# octanis_eps_revised.net
KiCad netlist of a schematic drawn in EAGLE
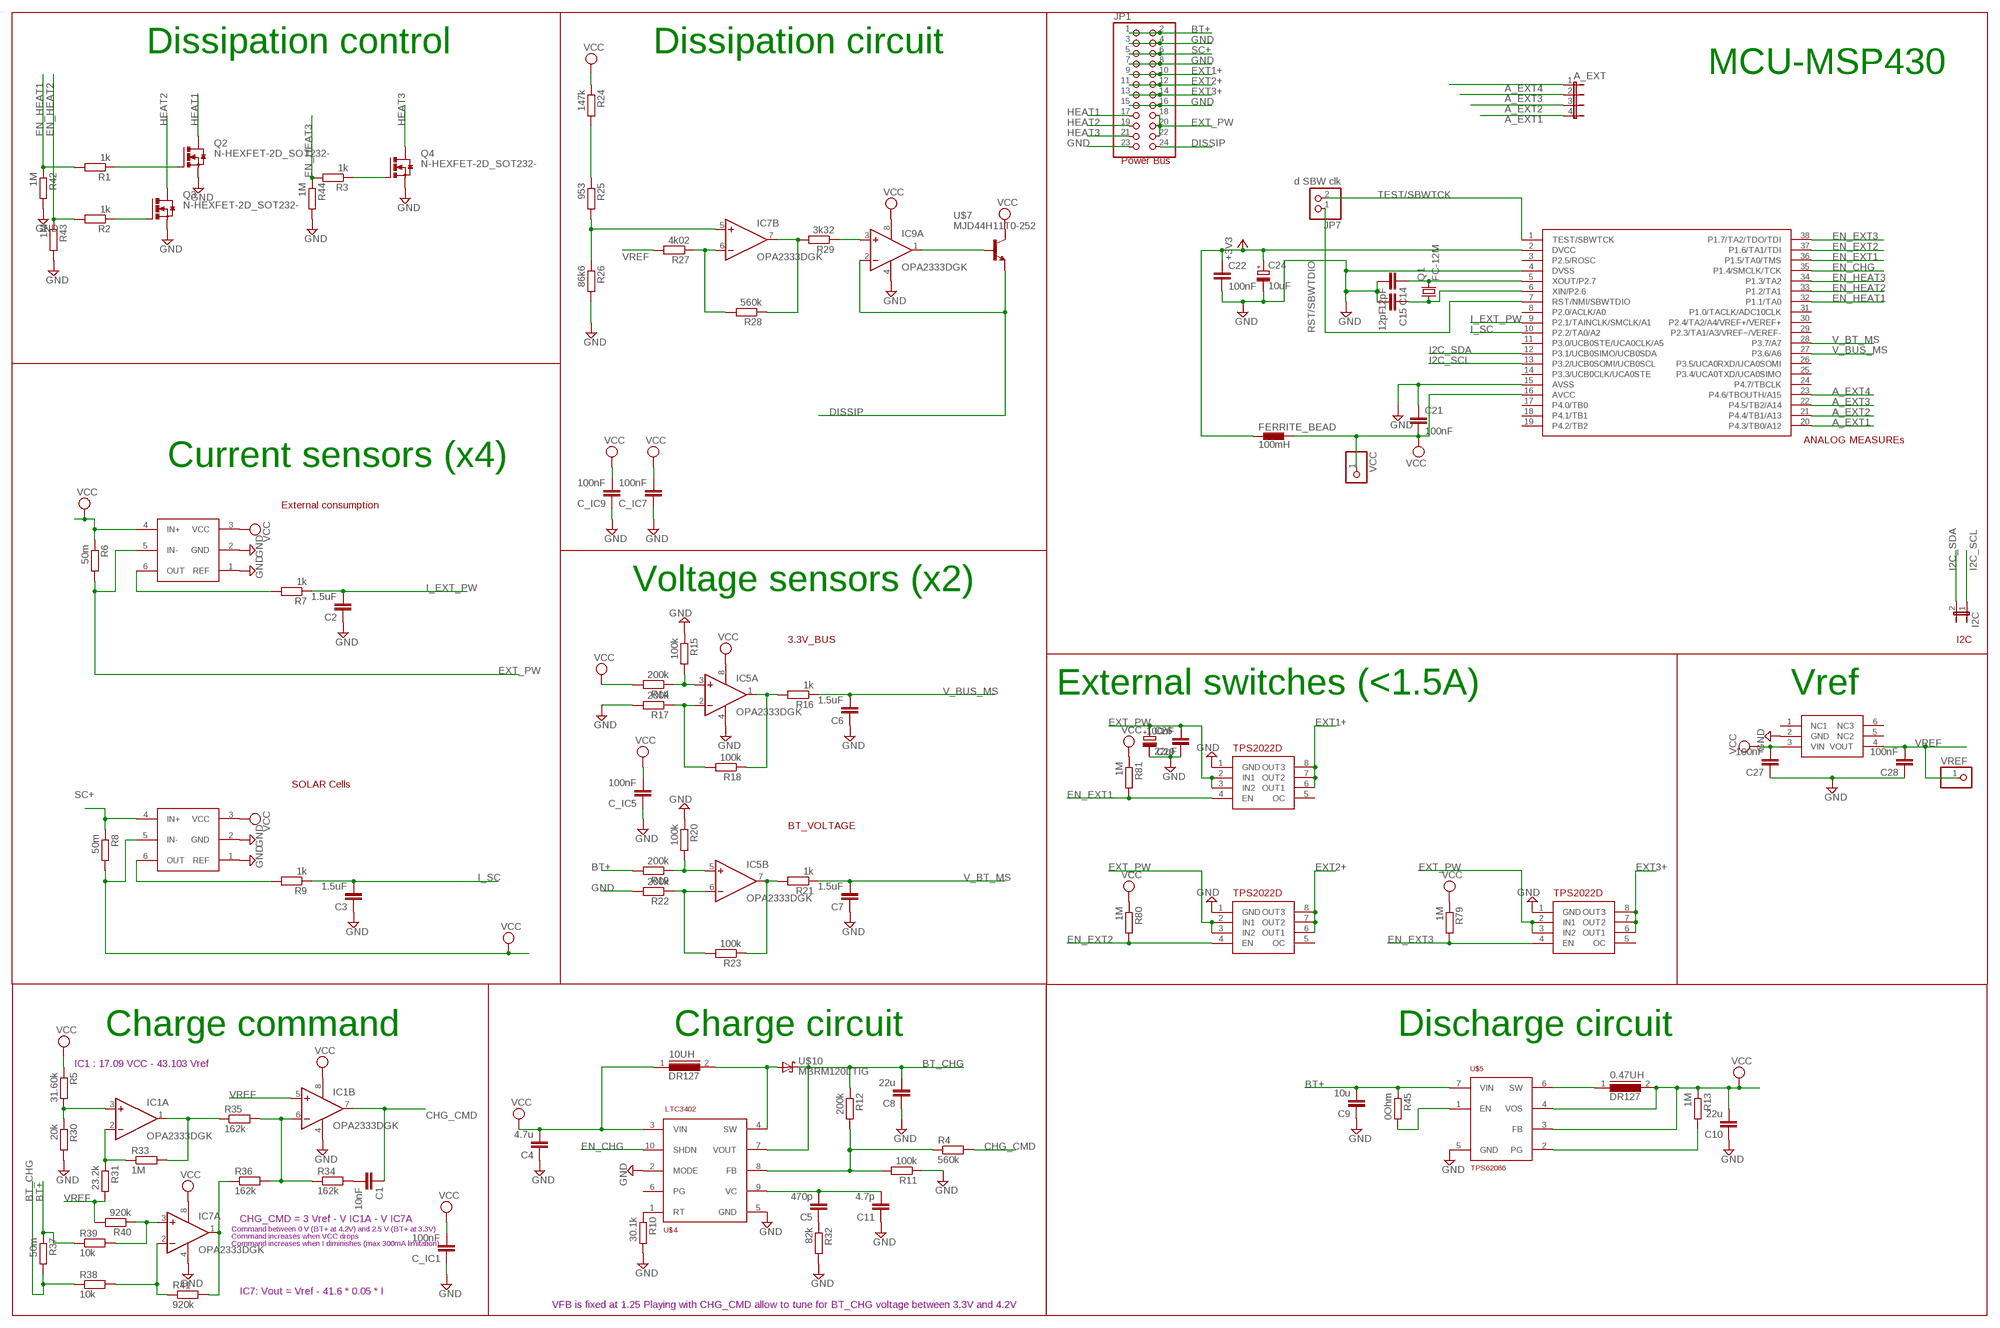
[diagram p0: schematic, sheet 1]

(export (version "E")
  (design (tool "Eeschema 10.0.6"))
  (components
    (comp (ref "0.47UH")
      (value "DR127")
      (footprint "eagle-import:DR127")
      (libsource (lib "eagle-import") (part "DR127"))
    )
    (comp (ref "10UH")
      (value "DR127")
      (footprint "eagle-import:DR127")
      (libsource (lib "eagle-import") (part "DR127"))
    )
    (comp (ref "A_EXT")
      (value "JP4E")
      (footprint "eagle-import:JP4")
      (libsource (lib "eagle-import") (part "JP4E"))
    )
    (comp (ref "C1")
      (value "10nF")
      (footprint "eagle-import:C0603")
      (libsource (lib "eagle-import") (part "C-EUC0603"))
    )
    (comp (ref "C2")
      (value "1.5uF")
      (footprint "eagle-import:C0603")
      (libsource (lib "eagle-import") (part "C-EUC0603"))
    )
    (comp (ref "C3")
      (value "1.5uF")
      (footprint "eagle-import:C0603")
      (libsource (lib "eagle-import") (part "C-EUC0603"))
    )
    (comp (ref "C4")
      (value "4.7u")
      (footprint "eagle-import:C1206")
      (libsource (lib "eagle-import") (part "C-EUC1206"))
    )
    (comp (ref "C5")
      (value "470p")
      (footprint "eagle-import:C0603")
      (libsource (lib "eagle-import") (part "C-EUC0603"))
    )
    (comp (ref "C6")
      (value "1.5uF")
      (footprint "eagle-import:C0603")
      (libsource (lib "eagle-import") (part "C-EUC0603"))
    )
    (comp (ref "C7")
      (value "1.5uF")
      (footprint "eagle-import:C0603")
      (libsource (lib "eagle-import") (part "C-EUC0603"))
    )
    (comp (ref "C8")
      (value "22u")
      (footprint "eagle-import:C0603")
      (libsource (lib "eagle-import") (part "C-EUC0603"))
    )
    (comp (ref "C9")
      (value "10u")
      (footprint "eagle-import:C1206")
      (libsource (lib "eagle-import") (part "C-EUC1206"))
    )
    (comp (ref "C10")
      (value "22u")
      (footprint "eagle-import:C1206")
      (libsource (lib "eagle-import") (part "C-EUC1206"))
    )
    (comp (ref "C11")
      (value "4.7p")
      (footprint "eagle-import:C0603")
      (libsource (lib "eagle-import") (part "C-EUC0603"))
    )
    (comp (ref "C14")
      (value "12pF")
      (footprint "eagle-import:C0603")
      (libsource (lib "eagle-import") (part "C-EUC0603"))
    )
    (comp (ref "C15")
      (value "12pF")
      (footprint "eagle-import:C0603")
      (libsource (lib "eagle-import") (part "C-EUC0603"))
    )
    (comp (ref "C21")
      (value "100nF")
      (footprint "eagle-import:C0603")
      (libsource (lib "eagle-import") (part "C-EUC0603"))
    )
    (comp (ref "C22")
      (value "100nF")
      (footprint "eagle-import:C0603")
      (libsource (lib "eagle-import") (part "C-EUC0603"))
    )
    (comp (ref "C24")
      (value "10uF")
      (footprint "eagle-import:A_3216-18R")
      (libsource (lib "eagle-import") (part "CPOL-EUA/3216-18R"))
    )
    (comp (ref "C26")
      (value "22uF")
      (footprint "eagle-import:A_3216-18R")
      (libsource (lib "eagle-import") (part "CPOL-EUA/3216-18R"))
    )
    (comp (ref "C27")
      (value "100nF")
      (footprint "eagle-import:C0603")
      (libsource (lib "eagle-import") (part "C-EUC0603"))
    )
    (comp (ref "C28")
      (value "100nF")
      (footprint "eagle-import:C0603")
      (libsource (lib "eagle-import") (part "C-EUC0603"))
    )
    (comp (ref "C29")
      (value "100nF")
      (footprint "eagle-import:C0603")
      (libsource (lib "eagle-import") (part "C-EUC0603"))
    )
    (comp (ref "C_IC1")
      (value "100nF")
      (footprint "eagle-import:C0603")
      (libsource (lib "eagle-import") (part "C-EUC0603"))
    )
    (comp (ref "C_IC5")
      (value "100nF")
      (footprint "eagle-import:C0603")
      (libsource (lib "eagle-import") (part "C-EUC0603"))
    )
    (comp (ref "C_IC7")
      (value "100nF")
      (footprint "eagle-import:C0603")
      (libsource (lib "eagle-import") (part "C-EUC0603"))
    )
    (comp (ref "C_IC9")
      (value "100nF")
      (footprint "eagle-import:C0603")
      (libsource (lib "eagle-import") (part "C-EUC0603"))
    )
    (comp (ref "FERRITE_BEAD")
      (value "100mH")
      (footprint "eagle-import:0402")
      (libsource (lib "eagle-import") (part "BLM15HD601SN1"))
    )
    (comp (ref "I2C")
      (value "JP1E")
      (footprint "eagle-import:JP1")
      (libsource (lib "eagle-import") (part "JP1E"))
    )
    (comp (ref "IC1")
      (value "OPA2333DGK")
      (footprint "eagle-import:MSOP08")
      (libsource (lib "eagle-import") (part "OPA2333DGK"))
    )
    (comp (ref "IC5")
      (value "OPA2333DGK")
      (footprint "eagle-import:MSOP08")
      (libsource (lib "eagle-import") (part "OPA2333DGK"))
    )
    (comp (ref "IC7")
      (value "OPA2333DGK")
      (footprint "eagle-import:MSOP08")
      (libsource (lib "eagle-import") (part "OPA2333DGK"))
    )
    (comp (ref "IC9")
      (value "OPA2333DGK")
      (footprint "eagle-import:MSOP08")
      (libsource (lib "eagle-import") (part "OPA2333DGK"))
    )
    (comp (ref "JP1")
      (value "PINHD-2X12")
      (footprint "eagle-import:2X12")
      (libsource (lib "eagle-import") (part "PINHD-2X12"))
    )
    (comp (ref "JP7")
      (value "d SBW clk")
      (footprint "eagle-import:1X02")
      (libsource (lib "eagle-import") (part "PINHD-1X2"))
    )
    (comp (ref "Q1")
      (value "FC-12M")
      (footprint "eagle-import:FC-12M")
      (libsource (lib "eagle-import") (part "FC-12M"))
    )
    (comp (ref "Q2")
      (value "N-HEXFET-2D_SOT232-")
      (footprint "eagle-import:SOT223")
      (libsource (lib "eagle-import") (part "N-HEXFET-2D_?-SOT232"))
    )
    (comp (ref "Q3")
      (value "N-HEXFET-2D_SOT232-")
      (footprint "eagle-import:SOT223")
      (libsource (lib "eagle-import") (part "N-HEXFET-2D_?-SOT232"))
    )
    (comp (ref "Q4")
      (value "N-HEXFET-2D_SOT232-")
      (footprint "eagle-import:SOT223")
      (libsource (lib "eagle-import") (part "N-HEXFET-2D_?-SOT232"))
    )
    (comp (ref "R1")
      (value "1k")
      (footprint "eagle-import:R0603")
      (libsource (lib "eagle-import") (part "R-EU_R0603"))
    )
    (comp (ref "R2")
      (value "1k")
      (footprint "eagle-import:R0603")
      (libsource (lib "eagle-import") (part "R-EU_R0603"))
    )
    (comp (ref "R3")
      (value "1k")
      (footprint "eagle-import:R0603")
      (libsource (lib "eagle-import") (part "R-EU_R0603"))
    )
    (comp (ref "R4")
      (value "560k")
      (footprint "eagle-import:R0603")
      (libsource (lib "eagle-import") (part "R-EU_R0603"))
    )
    (comp (ref "R5")
      (value "31.60k")
      (footprint "eagle-import:R0603")
      (libsource (lib "eagle-import") (part "R-EU_R0603"))
    )
    (comp (ref "R6")
      (value "50m")
      (footprint "eagle-import:R1206")
      (libsource (lib "eagle-import") (part "R-EU_R1206"))
    )
    (comp (ref "R7")
      (value "1k")
      (footprint "eagle-import:R0603")
      (libsource (lib "eagle-import") (part "R-EU_R0603"))
    )
    (comp (ref "R8")
      (value "50m")
      (footprint "eagle-import:R1206")
      (libsource (lib "eagle-import") (part "R-EU_R1206"))
    )
    (comp (ref "R9")
      (value "1k")
      (footprint "eagle-import:R0603")
      (libsource (lib "eagle-import") (part "R-EU_R0603"))
    )
    (comp (ref "R10")
      (value "30.1k")
      (footprint "eagle-import:R0603")
      (libsource (lib "eagle-import") (part "R-EU_R0603"))
    )
    (comp (ref "R11")
      (value "100k")
      (footprint "eagle-import:R0603")
      (libsource (lib "eagle-import") (part "R-EU_R0603"))
    )
    (comp (ref "R12")
      (value "200k")
      (footprint "eagle-import:R0603")
      (libsource (lib "eagle-import") (part "R-EU_R0603"))
    )
    (comp (ref "R13")
      (value "1M")
      (footprint "eagle-import:R0603")
      (libsource (lib "eagle-import") (part "R-EU_R0603"))
    )
    (comp (ref "R14")
      (value "200k")
      (footprint "eagle-import:R0603")
      (libsource (lib "eagle-import") (part "R-EU_R0603"))
    )
    (comp (ref "R15")
      (value "100k")
      (footprint "eagle-import:R0603")
      (libsource (lib "eagle-import") (part "R-EU_R0603"))
    )
    (comp (ref "R16")
      (value "1k")
      (footprint "eagle-import:R0603")
      (libsource (lib "eagle-import") (part "R-EU_R0603"))
    )
    (comp (ref "R17")
      (value "200k")
      (footprint "eagle-import:R0603")
      (libsource (lib "eagle-import") (part "R-EU_R0603"))
    )
    (comp (ref "R18")
      (value "100k")
      (footprint "eagle-import:R0603")
      (libsource (lib "eagle-import") (part "R-EU_R0603"))
    )
    (comp (ref "R19")
      (value "200k")
      (footprint "eagle-import:R0603")
      (libsource (lib "eagle-import") (part "R-EU_R0603"))
    )
    (comp (ref "R20")
      (value "100k")
      (footprint "eagle-import:R0603")
      (libsource (lib "eagle-import") (part "R-EU_R0603"))
    )
    (comp (ref "R21")
      (value "1k")
      (footprint "eagle-import:R0603")
      (libsource (lib "eagle-import") (part "R-EU_R0603"))
    )
    (comp (ref "R22")
      (value "200k")
      (footprint "eagle-import:R0603")
      (libsource (lib "eagle-import") (part "R-EU_R0603"))
    )
    (comp (ref "R23")
      (value "100k")
      (footprint "eagle-import:R0603")
      (libsource (lib "eagle-import") (part "R-EU_R0603"))
    )
    (comp (ref "R24")
      (value "147k")
      (footprint "eagle-import:R0603")
      (libsource (lib "eagle-import") (part "R-EU_R0603"))
    )
    (comp (ref "R25")
      (value "953")
      (footprint "eagle-import:R0603")
      (libsource (lib "eagle-import") (part "R-EU_R0603"))
    )
    (comp (ref "R26")
      (value "86k6")
      (footprint "eagle-import:R0603")
      (libsource (lib "eagle-import") (part "R-EU_R0603"))
    )
    (comp (ref "R27")
      (value "4k02")
      (footprint "eagle-import:R0603")
      (libsource (lib "eagle-import") (part "R-EU_R0603"))
    )
    (comp (ref "R28")
      (value "560k")
      (footprint "eagle-import:R0603")
      (libsource (lib "eagle-import") (part "R-EU_R0603"))
    )
    (comp (ref "R29")
      (value "3k32")
      (footprint "eagle-import:R0603")
      (libsource (lib "eagle-import") (part "R-EU_R0603"))
    )
    (comp (ref "R30")
      (value "20k")
      (footprint "eagle-import:R0603")
      (libsource (lib "eagle-import") (part "R-EU_R0603"))
    )
    (comp (ref "R31")
      (value "23.2k")
      (footprint "eagle-import:R0603")
      (libsource (lib "eagle-import") (part "R-EU_R0603"))
    )
    (comp (ref "R32")
      (value "82k")
      (footprint "eagle-import:R0603")
      (libsource (lib "eagle-import") (part "R-EU_R0603"))
    )
    (comp (ref "R33")
      (value "1M")
      (footprint "eagle-import:R0603")
      (libsource (lib "eagle-import") (part "R-EU_R0603"))
    )
    (comp (ref "R34")
      (value "162k")
      (footprint "eagle-import:R0603")
      (libsource (lib "eagle-import") (part "R-EU_R0603"))
    )
    (comp (ref "R35")
      (value "162k")
      (footprint "eagle-import:R0603")
      (libsource (lib "eagle-import") (part "R-EU_R0603"))
    )
    (comp (ref "R36")
      (value "162k")
      (footprint "eagle-import:R0603")
      (libsource (lib "eagle-import") (part "R-EU_R0603"))
    )
    (comp (ref "R37")
      (value "50m")
      (footprint "eagle-import:R1206")
      (libsource (lib "eagle-import") (part "R-EU_R1206"))
    )
    (comp (ref "R38")
      (value "10k")
      (footprint "eagle-import:R0603")
      (libsource (lib "eagle-import") (part "R-EU_R0603"))
    )
    (comp (ref "R39")
      (value "10k")
      (footprint "eagle-import:R0603")
      (libsource (lib "eagle-import") (part "R-EU_R0603"))
    )
    (comp (ref "R40")
      (value "920k")
      (footprint "eagle-import:R0603")
      (libsource (lib "eagle-import") (part "R-EU_R0603"))
    )
    (comp (ref "R41")
      (value "920k")
      (footprint "eagle-import:R0603")
      (libsource (lib "eagle-import") (part "R-EU_R0603"))
    )
    (comp (ref "R42")
      (value "1M")
      (footprint "eagle-import:R0603")
      (libsource (lib "eagle-import") (part "R-EU_R0603"))
    )
    (comp (ref "R43")
      (value "1M")
      (footprint "eagle-import:R0603")
      (libsource (lib "eagle-import") (part "R-EU_R0603"))
    )
    (comp (ref "R44")
      (value "1M")
      (footprint "eagle-import:R0603")
      (libsource (lib "eagle-import") (part "R-EU_R0603"))
    )
    (comp (ref "R45")
      (value "0Ohm")
      (footprint "eagle-import:R0603")
      (libsource (lib "eagle-import") (part "R-EU_R0603"))
    )
    (comp (ref "R79")
      (value "1M")
      (footprint "eagle-import:R0603")
      (libsource (lib "eagle-import") (part "R-EU_R0603"))
    )
    (comp (ref "R80")
      (value "1M")
      (footprint "eagle-import:R0603")
      (libsource (lib "eagle-import") (part "R-EU_R0603"))
    )
    (comp (ref "R81")
      (value "1M")
      (footprint "eagle-import:R0603")
      (libsource (lib "eagle-import") (part "R-EU_R0603"))
    )
    (comp (ref "U$2")
      (value "INA213")
      (footprint "eagle-import:SC70-6")
      (libsource (lib "eagle-import") (part "INA213"))
    )
    (comp (ref "U$3")
      (value "INA213")
      (footprint "eagle-import:SC70-6")
      (libsource (lib "eagle-import") (part "INA213"))
    )
    (comp (ref "U$4")
      (value "LTC3402")
      (footprint "eagle-import:MSOP10")
      (libsource (lib "eagle-import") (part "LTC3402"))
    )
    (comp (ref "U$5")
      (value "TPS62086")
      (footprint "eagle-import:QFN-7")
      (libsource (lib "eagle-import") (part "TPS62086"))
    )
    (comp (ref "U$6")
      (value "MSP430G2544")
      (footprint "eagle-import:TSSOP38")
      (libsource (lib "eagle-import") (part "MSP430G2544"))
    )
    (comp (ref "U$7")
      (value "MJD44H11T0-252")
      (footprint "eagle-import:TO252")
      (libsource (lib "eagle-import") (part "MJD44H11T0-252"))
    )
    (comp (ref "U$10")
      (value "MBRM120LTIG")
      (footprint "eagle-import:DO216AA")
      (libsource (lib "eagle-import") (part "MBRM120LTIG"))
    )
    (comp (ref "U$16")
      (value "TPS2022D")
      (footprint "eagle-import:SO8")
      (libsource (lib "eagle-import") (part "TPS2022D"))
    )
    (comp (ref "U$17")
      (value "TPS2022D")
      (footprint "eagle-import:SO8")
      (libsource (lib "eagle-import") (part "TPS2022D"))
    )
    (comp (ref "U$18")
      (value "TPS2022D")
      (footprint "eagle-import:SO8")
      (libsource (lib "eagle-import") (part "TPS2022D"))
    )
    (comp (ref "U$19")
      (value "ADR127B")
      (footprint "eagle-import:TSOT23-6")
      (libsource (lib "eagle-import") (part "ADR127B"))
    )
    (comp (ref "VCC")
      (value "PINHD-1X1")
      (footprint "eagle-import:1X01")
      (libsource (lib "eagle-import") (part "PINHD-1X1"))
    )
    (comp (ref "VREF")
      (value "PINHD-1X1")
      (footprint "eagle-import:1X01")
      (libsource (lib "eagle-import") (part "PINHD-1X1"))
    )
  )
  (nets
    (net (code "1") (name "+3V3") (class "Default")
      (node (ref "C22") (pin "1") (pinfunction "1_1") (pintype "passive"))
      (node (ref "C24") (pin "+") (pinfunction "+_+") (pintype "passive"))
      (node (ref "FERRITE_BEAD") (pin "1") (pinfunction "1_1") (pintype "passive"))
      (node (ref "U$6") (pin "2") (pinfunction "DVCC_2") (pintype "bidirectional"))
    )
    (net (code "2") (name "/A_EXT1") (class "Default")
      (node (ref "A_EXT") (pin "4") (pinfunction "4_4") (pintype "passive"))
      (node (ref "U$6") (pin "20") (pinfunction "P4.3/TB0/A12_20") (pintype "bidirectional"))
    )
    (net (code "3") (name "/A_EXT2") (class "Default")
      (node (ref "A_EXT") (pin "3") (pinfunction "3_3") (pintype "passive"))
      (node (ref "U$6") (pin "21") (pinfunction "P4.4/TB1/A13_21") (pintype "bidirectional"))
    )
    (net (code "4") (name "/A_EXT3") (class "Default")
      (node (ref "A_EXT") (pin "2") (pinfunction "2_2") (pintype "passive"))
      (node (ref "U$6") (pin "22") (pinfunction "P4.5/TB2/A14_22") (pintype "bidirectional"))
    )
    (net (code "5") (name "/A_EXT4") (class "Default")
      (node (ref "A_EXT") (pin "1") (pinfunction "1_1") (pintype "passive"))
      (node (ref "U$6") (pin "23") (pinfunction "P4.6/TBOUTH/A15_23") (pintype "bidirectional"))
    )
    (net (code "6") (name "/BT+") (class "Default")
      (node (ref "C9") (pin "2") (pinfunction "2_2") (pintype "passive"))
      (node (ref "JP1") (pin "1") (pinfunction "1_1") (pintype "passive"))
      (node (ref "JP1") (pin "2") (pinfunction "2_2") (pintype "passive"))
      (node (ref "R19") (pin "2") (pinfunction "2_2") (pintype "passive"))
      (node (ref "R37") (pin "1") (pinfunction "1_1") (pintype "passive"))
      (node (ref "R39") (pin "1") (pinfunction "1_1") (pintype "passive"))
      (node (ref "R45") (pin "1") (pinfunction "1_1") (pintype "passive"))
      (node (ref "U$5") (pin "7") (pinfunction "VIN_7") (pintype "bidirectional"))
    )
    (net (code "7") (name "/BT_CHG") (class "Default")
      (node (ref "C8") (pin "2") (pinfunction "2_2") (pintype "passive"))
      (node (ref "R12") (pin "1") (pinfunction "1_1") (pintype "passive"))
      (node (ref "R37") (pin "2") (pinfunction "2_2") (pintype "passive"))
      (node (ref "R38") (pin "1") (pinfunction "1_1") (pintype "passive"))
      (node (ref "U$10") (pin "C") (pinfunction "K_C") (pintype "passive"))
      (node (ref "U$4") (pin "7") (pinfunction "VOUT_7") (pintype "bidirectional"))
    )
    (net (code "8") (name "/CHG_CMD") (class "Default")
      (node (ref "C1") (pin "1") (pinfunction "1_1") (pintype "passive"))
      (node (ref "IC1") (pin "7") (pinfunction "OUT_7") (pintype "output"))
      (node (ref "R4") (pin "2") (pinfunction "2_2") (pintype "passive"))
    )
    (net (code "9") (name "/DISSIP") (class "Default")
      (node (ref "IC9") (pin "2") (pinfunction "-IN_2") (pintype "input"))
      (node (ref "JP1") (pin "24") (pinfunction "24_24") (pintype "passive"))
      (node (ref "U$7") (pin "3") (pinfunction "E_3") (pintype "passive"))
    )
    (net (code "10") (name "/EN_CHG") (class "Default")
      (node (ref "U$4") (pin "10") (pinfunction "SHDN_10") (pintype "bidirectional"))
      (node (ref "U$6") (pin "35") (pinfunction "P1.4/SMCLK/TCK_35") (pintype "bidirectional"))
    )
    (net (code "11") (name "/EN_EXT1") (class "Default")
      (node (ref "R81") (pin "2") (pinfunction "2_2") (pintype "passive"))
      (node (ref "U$16") (pin "4") (pinfunction "EN_4") (pintype "bidirectional"))
      (node (ref "U$6") (pin "36") (pinfunction "P1.5/TA0/TMS_36") (pintype "bidirectional"))
    )
    (net (code "12") (name "/EN_EXT2") (class "Default")
      (node (ref "R80") (pin "2") (pinfunction "2_2") (pintype "passive"))
      (node (ref "U$17") (pin "4") (pinfunction "EN_4") (pintype "bidirectional"))
      (node (ref "U$6") (pin "37") (pinfunction "P1.6/TA1/TDI_37") (pintype "bidirectional"))
    )
    (net (code "13") (name "/EN_EXT3") (class "Default")
      (node (ref "R79") (pin "2") (pinfunction "2_2") (pintype "passive"))
      (node (ref "U$18") (pin "4") (pinfunction "EN_4") (pintype "bidirectional"))
      (node (ref "U$6") (pin "38") (pinfunction "P1.7/TA2/TDO/TDI_38") (pintype "bidirectional"))
    )
    (net (code "14") (name "/EN_HEAT1") (class "Default")
      (node (ref "R1") (pin "2") (pinfunction "2_2") (pintype "passive"))
      (node (ref "R42") (pin "1") (pinfunction "1_1") (pintype "passive"))
      (node (ref "U$6") (pin "32") (pinfunction "P1.1/TA0_32") (pintype "bidirectional"))
    )
    (net (code "15") (name "/EN_HEAT2") (class "Default")
      (node (ref "R2") (pin "2") (pinfunction "2_2") (pintype "passive"))
      (node (ref "R43") (pin "1") (pinfunction "1_1") (pintype "passive"))
      (node (ref "U$6") (pin "33") (pinfunction "P1.2/TA1_33") (pintype "bidirectional"))
    )
    (net (code "16") (name "/EN_HEAT3") (class "Default")
      (node (ref "R3") (pin "2") (pinfunction "2_2") (pintype "passive"))
      (node (ref "R44") (pin "1") (pinfunction "1_1") (pintype "passive"))
      (node (ref "U$6") (pin "34") (pinfunction "P1.3/TA2_34") (pintype "bidirectional"))
    )
    (net (code "17") (name "/EXT1+") (class "Default")
      (node (ref "JP1") (pin "10") (pinfunction "10_10") (pintype "passive"))
      (node (ref "JP1") (pin "9") (pinfunction "9_9") (pintype "passive"))
      (node (ref "U$16") (pin "6") (pinfunction "OUT1_6") (pintype "bidirectional"))
      (node (ref "U$16") (pin "7") (pinfunction "OUT2_7") (pintype "bidirectional"))
      (node (ref "U$16") (pin "8") (pinfunction "OUT3_8") (pintype "bidirectional"))
    )
    (net (code "18") (name "/EXT2+") (class "Default")
      (node (ref "JP1") (pin "11") (pinfunction "11_11") (pintype "passive"))
      (node (ref "JP1") (pin "12") (pinfunction "12_12") (pintype "passive"))
      (node (ref "U$17") (pin "6") (pinfunction "OUT1_6") (pintype "bidirectional"))
      (node (ref "U$17") (pin "7") (pinfunction "OUT2_7") (pintype "bidirectional"))
      (node (ref "U$17") (pin "8") (pinfunction "OUT3_8") (pintype "bidirectional"))
    )
    (net (code "19") (name "/EXT3+") (class "Default")
      (node (ref "JP1") (pin "13") (pinfunction "13_13") (pintype "passive"))
      (node (ref "JP1") (pin "14") (pinfunction "14_14") (pintype "passive"))
      (node (ref "U$18") (pin "6") (pinfunction "OUT1_6") (pintype "bidirectional"))
      (node (ref "U$18") (pin "7") (pinfunction "OUT2_7") (pintype "bidirectional"))
      (node (ref "U$18") (pin "8") (pinfunction "OUT3_8") (pintype "bidirectional"))
    )
    (net (code "20") (name "/EXT_PW") (class "Default")
      (node (ref "C26") (pin "+") (pinfunction "+_+") (pintype "passive"))
      (node (ref "C29") (pin "2") (pinfunction "2_2") (pintype "passive"))
      (node (ref "JP1") (pin "18") (pinfunction "18_18") (pintype "passive"))
      (node (ref "JP1") (pin "20") (pinfunction "20_20") (pintype "passive"))
      (node (ref "JP1") (pin "22") (pinfunction "22_22") (pintype "passive"))
      (node (ref "R6") (pin "2") (pinfunction "2_2") (pintype "passive"))
      (node (ref "U$16") (pin "2") (pinfunction "IN1_2") (pintype "bidirectional"))
      (node (ref "U$16") (pin "3") (pinfunction "IN2_3") (pintype "bidirectional"))
      (node (ref "U$17") (pin "2") (pinfunction "IN1_2") (pintype "bidirectional"))
      (node (ref "U$17") (pin "3") (pinfunction "IN2_3") (pintype "bidirectional"))
      (node (ref "U$18") (pin "2") (pinfunction "IN1_2") (pintype "bidirectional"))
      (node (ref "U$18") (pin "3") (pinfunction "IN2_3") (pintype "bidirectional"))
      (node (ref "U$2") (pin "5") (pinfunction "IN-_5") (pintype "bidirectional"))
    )
    (net (code "21") (name "/HEAT1") (class "Default")
      (node (ref "JP1") (pin "17") (pinfunction "17_17") (pintype "passive"))
      (node (ref "Q2") (pin "2") (pinfunction "D_2") (pintype "passive"))
      (node (ref "Q2") (pin "4") (pinfunction "D_4") (pintype "passive"))
    )
    (net (code "22") (name "/HEAT2") (class "Default")
      (node (ref "JP1") (pin "19") (pinfunction "19_19") (pintype "passive"))
      (node (ref "Q3") (pin "2") (pinfunction "D_2") (pintype "passive"))
      (node (ref "Q3") (pin "4") (pinfunction "D_4") (pintype "passive"))
    )
    (net (code "23") (name "/HEAT3") (class "Default")
      (node (ref "JP1") (pin "21") (pinfunction "21_21") (pintype "passive"))
      (node (ref "Q4") (pin "2") (pinfunction "D_2") (pintype "passive"))
      (node (ref "Q4") (pin "4") (pinfunction "D_4") (pintype "passive"))
    )
    (net (code "24") (name "/I2C_SCL") (class "Default")
      (node (ref "I2C") (pin "1") (pinfunction "1_1") (pintype "passive"))
      (node (ref "U$6") (pin "13") (pinfunction "P3.2/UCB0SOMI/UCB0SCL_13") (pintype "bidirectional"))
    )
    (net (code "25") (name "/I2C_SDA") (class "Default")
      (node (ref "I2C") (pin "2") (pinfunction "2_2") (pintype "passive"))
      (node (ref "U$6") (pin "12") (pinfunction "P3.1/UCB0SIMO/UCB0SDA_12") (pintype "bidirectional"))
    )
    (net (code "26") (name "/I_EXT_PW") (class "Default")
      (node (ref "C2") (pin "2") (pinfunction "2_2") (pintype "passive"))
      (node (ref "R7") (pin "1") (pinfunction "1_1") (pintype "passive"))
      (node (ref "U$6") (pin "9") (pinfunction "P2.1/TAINCLK/SMCLK/A1_9") (pintype "bidirectional"))
    )
    (net (code "27") (name "/I_SC") (class "Default")
      (node (ref "C3") (pin "2") (pinfunction "2_2") (pintype "passive"))
      (node (ref "R9") (pin "1") (pinfunction "1_1") (pintype "passive"))
      (node (ref "U$6") (pin "10") (pinfunction "P2.2/TA0/A2_10") (pintype "bidirectional"))
    )
    (net (code "28") (name "/RST{slash}SBWTDIO") (class "Default")
      (node (ref "JP7") (pin "1") (pinfunction "1_1") (pintype "passive"))
      (node (ref "U$6") (pin "7") (pinfunction "RST/NMI/SBWTDIO_7") (pintype "bidirectional"))
    )
    (net (code "29") (name "/SC+") (class "Default")
      (node (ref "JP1") (pin "5") (pinfunction "5_5") (pintype "passive"))
      (node (ref "JP1") (pin "6") (pinfunction "6_6") (pintype "passive"))
      (node (ref "R8") (pin "1") (pinfunction "1_1") (pintype "passive"))
      (node (ref "U$3") (pin "4") (pinfunction "IN+_4") (pintype "bidirectional"))
    )
    (net (code "30") (name "/TEST{slash}SBWTCK") (class "Default")
      (node (ref "JP7") (pin "2") (pinfunction "2_2") (pintype "passive"))
      (node (ref "U$6") (pin "1") (pinfunction "TEST/SBWTCK_1") (pintype "bidirectional"))
    )
    (net (code "31") (name "/VREF") (class "Default")
      (node (ref "C28") (pin "2") (pinfunction "2_2") (pintype "passive"))
      (node (ref "IC1") (pin "5") (pinfunction "+IN_5") (pintype "input"))
      (node (ref "R27") (pin "2") (pinfunction "2_2") (pintype "passive"))
      (node (ref "R31") (pin "2") (pinfunction "2_2") (pintype "passive"))
      (node (ref "R40") (pin "2") (pinfunction "2_2") (pintype "passive"))
      (node (ref "U$19") (pin "4") (pinfunction "VOUT_4") (pintype "bidirectional"))
      (node (ref "VREF") (pin "1") (pinfunction "1_1") (pintype "passive"))
    )
    (net (code "32") (name "/V_BT_MS") (class "Default")
      (node (ref "C7") (pin "2") (pinfunction "2_2") (pintype "passive"))
      (node (ref "R21") (pin "1") (pinfunction "1_1") (pintype "passive"))
      (node (ref "U$6") (pin "28") (pinfunction "P3.7/A7_28") (pintype "bidirectional"))
    )
    (net (code "33") (name "/V_BUS_MS") (class "Default")
      (node (ref "C6") (pin "2") (pinfunction "2_2") (pintype "passive"))
      (node (ref "R16") (pin "1") (pinfunction "1_1") (pintype "passive"))
      (node (ref "U$6") (pin "27") (pinfunction "P3.6/A6_27") (pintype "bidirectional"))
    )
    (net (code "34") (name "GND") (class "Default")
      (node (ref "C10") (pin "1") (pinfunction "1_1") (pintype "passive"))
      (node (ref "C11") (pin "1") (pinfunction "1_1") (pintype "passive"))
      (node (ref "C14") (pin "2") (pinfunction "2_2") (pintype "passive"))
      (node (ref "C15") (pin "2") (pinfunction "2_2") (pintype "passive"))
      (node (ref "C2") (pin "1") (pinfunction "1_1") (pintype "passive"))
      (node (ref "C21") (pin "1") (pinfunction "1_1") (pintype "passive"))
      (node (ref "C22") (pin "2") (pinfunction "2_2") (pintype "passive"))
      (node (ref "C24") (pin "-") (pinfunction "-_-") (pintype "passive"))
      (node (ref "C26") (pin "-") (pinfunction "-_-") (pintype "passive"))
      (node (ref "C27") (pin "1") (pinfunction "1_1") (pintype "passive"))
      (node (ref "C28") (pin "1") (pinfunction "1_1") (pintype "passive"))
      (node (ref "C29") (pin "1") (pinfunction "1_1") (pintype "passive"))
      (node (ref "C3") (pin "1") (pinfunction "1_1") (pintype "passive"))
      (node (ref "C4") (pin "1") (pinfunction "1_1") (pintype "passive"))
      (node (ref "C6") (pin "1") (pinfunction "1_1") (pintype "passive"))
      (node (ref "C7") (pin "1") (pinfunction "1_1") (pintype "passive"))
      (node (ref "C8") (pin "1") (pinfunction "1_1") (pintype "passive"))
      (node (ref "C9") (pin "1") (pinfunction "1_1") (pintype "passive"))
      (node (ref "C_IC1") (pin "1") (pinfunction "1_1") (pintype "passive"))
      (node (ref "C_IC5") (pin "1") (pinfunction "1_1") (pintype "passive"))
      (node (ref "C_IC7") (pin "1") (pinfunction "1_1") (pintype "passive"))
      (node (ref "C_IC9") (pin "1") (pinfunction "1_1") (pintype "passive"))
      (node (ref "IC1") (pin "4") (pinfunction "V-_4") (pintype "power_in"))
      (node (ref "IC5") (pin "4") (pinfunction "V-_4") (pintype "power_in"))
      (node (ref "IC7") (pin "4") (pinfunction "V-_4") (pintype "power_in"))
      (node (ref "IC9") (pin "4") (pinfunction "V-_4") (pintype "power_in"))
      (node (ref "JP1") (pin "15") (pinfunction "15_15") (pintype "passive"))
      (node (ref "JP1") (pin "16") (pinfunction "16_16") (pintype "passive"))
      (node (ref "JP1") (pin "23") (pinfunction "23_23") (pintype "passive"))
      (node (ref "JP1") (pin "3") (pinfunction "3_3") (pintype "passive"))
      (node (ref "JP1") (pin "4") (pinfunction "4_4") (pintype "passive"))
      (node (ref "JP1") (pin "7") (pinfunction "7_7") (pintype "passive"))
      (node (ref "JP1") (pin "8") (pinfunction "8_8") (pintype "passive"))
      (node (ref "Q2") (pin "3") (pinfunction "S_3") (pintype "passive"))
      (node (ref "Q3") (pin "3") (pinfunction "S_3") (pintype "passive"))
      (node (ref "Q4") (pin "3") (pinfunction "S_3") (pintype "passive"))
      (node (ref "R10") (pin "2") (pinfunction "2_2") (pintype "passive"))
      (node (ref "R11") (pin "1") (pinfunction "1_1") (pintype "passive"))
      (node (ref "R15") (pin "1") (pinfunction "1_1") (pintype "passive"))
      (node (ref "R17") (pin "2") (pinfunction "2_2") (pintype "passive"))
      (node (ref "R20") (pin "1") (pinfunction "1_1") (pintype "passive"))
      (node (ref "R22") (pin "2") (pinfunction "2_2") (pintype "passive"))
      (node (ref "R26") (pin "2") (pinfunction "2_2") (pintype "passive"))
      (node (ref "R30") (pin "2") (pinfunction "2_2") (pintype "passive"))
      (node (ref "R32") (pin "2") (pinfunction "2_2") (pintype "passive"))
      (node (ref "R42") (pin "2") (pinfunction "2_2") (pintype "passive"))
      (node (ref "R43") (pin "2") (pinfunction "2_2") (pintype "passive"))
      (node (ref "R44") (pin "2") (pinfunction "2_2") (pintype "passive"))
      (node (ref "U$16") (pin "1") (pinfunction "GND_1") (pintype "bidirectional"))
      (node (ref "U$17") (pin "1") (pinfunction "GND_1") (pintype "bidirectional"))
      (node (ref "U$18") (pin "1") (pinfunction "GND_1") (pintype "bidirectional"))
      (node (ref "U$19") (pin "2") (pinfunction "GND_2") (pintype "bidirectional"))
      (node (ref "U$2") (pin "1") (pinfunction "REF_1") (pintype "bidirectional"))
      (node (ref "U$2") (pin "2") (pinfunction "GND_2") (pintype "bidirectional"))
      (node (ref "U$3") (pin "1") (pinfunction "REF_1") (pintype "bidirectional"))
      (node (ref "U$3") (pin "2") (pinfunction "GND_2") (pintype "bidirectional"))
      (node (ref "U$4") (pin "2") (pinfunction "MODE_2") (pintype "bidirectional"))
      (node (ref "U$4") (pin "5") (pinfunction "GND_5") (pintype "bidirectional"))
      (node (ref "U$5") (pin "5") (pinfunction "GND_5") (pintype "bidirectional"))
      (node (ref "U$6") (pin "15") (pinfunction "AVSS_15") (pintype "bidirectional"))
      (node (ref "U$6") (pin "4") (pinfunction "DVSS_4") (pintype "bidirectional"))
    )
    (net (code "35") (name "Net-(C1-Pad2)") (class "Default")
      (node (ref "C1") (pin "2") (pinfunction "2_2") (pintype "passive"))
      (node (ref "R34") (pin "2") (pinfunction "2_2") (pintype "passive"))
    )
    (net (code "36") (name "Net-(C5-Pad1)") (class "Default")
      (node (ref "C5") (pin "1") (pinfunction "1_1") (pintype "passive"))
      (node (ref "R32") (pin "1") (pinfunction "1_1") (pintype "passive"))
    )
    (net (code "37") (name "Net-(IC1A-+IN)") (class "Default")
      (node (ref "IC1") (pin "3") (pinfunction "+IN_3") (pintype "input"))
      (node (ref "R30") (pin "1") (pinfunction "1_1") (pintype "passive"))
      (node (ref "R5") (pin "2") (pinfunction "2_2") (pintype "passive"))
    )
    (net (code "38") (name "Net-(IC1A--IN)") (class "Default")
      (node (ref "IC1") (pin "2") (pinfunction "-IN_2") (pintype "input"))
      (node (ref "R31") (pin "1") (pinfunction "1_1") (pintype "passive"))
      (node (ref "R33") (pin "1") (pinfunction "1_1") (pintype "passive"))
    )
    (net (code "39") (name "Net-(IC1A-OUT)") (class "Default")
      (node (ref "IC1") (pin "1") (pinfunction "OUT_1") (pintype "output"))
      (node (ref "R33") (pin "2") (pinfunction "2_2") (pintype "passive"))
      (node (ref "R35") (pin "1") (pinfunction "1_1") (pintype "passive"))
    )
    (net (code "40") (name "Net-(IC1B--IN)") (class "Default")
      (node (ref "IC1") (pin "6") (pinfunction "-IN_6") (pintype "input"))
      (node (ref "R34") (pin "1") (pinfunction "1_1") (pintype "passive"))
      (node (ref "R35") (pin "2") (pinfunction "2_2") (pintype "passive"))
      (node (ref "R36") (pin "2") (pinfunction "2_2") (pintype "passive"))
    )
    (net (code "41") (name "Net-(IC5A-+IN)") (class "Default")
      (node (ref "IC5") (pin "3") (pinfunction "+IN_3") (pintype "input"))
      (node (ref "R14") (pin "1") (pinfunction "1_1") (pintype "passive"))
      (node (ref "R15") (pin "2") (pinfunction "2_2") (pintype "passive"))
    )
    (net (code "42") (name "Net-(IC5A--IN)") (class "Default")
      (node (ref "IC5") (pin "2") (pinfunction "-IN_2") (pintype "input"))
      (node (ref "R17") (pin "1") (pinfunction "1_1") (pintype "passive"))
      (node (ref "R18") (pin "2") (pinfunction "2_2") (pintype "passive"))
    )
    (net (code "43") (name "Net-(IC5A-OUT)") (class "Default")
      (node (ref "IC5") (pin "1") (pinfunction "OUT_1") (pintype "output"))
      (node (ref "R16") (pin "2") (pinfunction "2_2") (pintype "passive"))
      (node (ref "R18") (pin "1") (pinfunction "1_1") (pintype "passive"))
    )
    (net (code "44") (name "Net-(IC5B-+IN)") (class "Default")
      (node (ref "IC5") (pin "5") (pinfunction "+IN_5") (pintype "input"))
      (node (ref "R19") (pin "1") (pinfunction "1_1") (pintype "passive"))
      (node (ref "R20") (pin "2") (pinfunction "2_2") (pintype "passive"))
    )
    (net (code "45") (name "Net-(IC5B--IN)") (class "Default")
      (node (ref "IC5") (pin "6") (pinfunction "-IN_6") (pintype "input"))
      (node (ref "R22") (pin "1") (pinfunction "1_1") (pintype "passive"))
      (node (ref "R23") (pin "2") (pinfunction "2_2") (pintype "passive"))
    )
    (net (code "46") (name "Net-(IC5B-OUT)") (class "Default")
      (node (ref "IC5") (pin "7") (pinfunction "OUT_7") (pintype "output"))
      (node (ref "R21") (pin "2") (pinfunction "2_2") (pintype "passive"))
      (node (ref "R23") (pin "1") (pinfunction "1_1") (pintype "passive"))
    )
    (net (code "47") (name "Net-(IC7A-+IN)") (class "Default")
      (node (ref "IC7") (pin "3") (pinfunction "+IN_3") (pintype "input"))
      (node (ref "R39") (pin "2") (pinfunction "2_2") (pintype "passive"))
      (node (ref "R40") (pin "1") (pinfunction "1_1") (pintype "passive"))
    )
    (net (code "48") (name "Net-(IC7A--IN)") (class "Default")
      (node (ref "IC7") (pin "2") (pinfunction "-IN_2") (pintype "input"))
      (node (ref "R38") (pin "2") (pinfunction "2_2") (pintype "passive"))
      (node (ref "R41") (pin "1") (pinfunction "1_1") (pintype "passive"))
    )
    (net (code "49") (name "Net-(IC7A-OUT)") (class "Default")
      (node (ref "IC7") (pin "1") (pinfunction "OUT_1") (pintype "output"))
      (node (ref "R36") (pin "1") (pinfunction "1_1") (pintype "passive"))
      (node (ref "R41") (pin "2") (pinfunction "2_2") (pintype "passive"))
    )
    (net (code "50") (name "Net-(IC7B-+IN)") (class "Default")
      (node (ref "IC7") (pin "5") (pinfunction "+IN_5") (pintype "input"))
      (node (ref "R25") (pin "2") (pinfunction "2_2") (pintype "passive"))
      (node (ref "R26") (pin "1") (pinfunction "1_1") (pintype "passive"))
    )
    (net (code "51") (name "Net-(IC7B--IN)") (class "Default")
      (node (ref "IC7") (pin "6") (pinfunction "-IN_6") (pintype "input"))
      (node (ref "R27") (pin "1") (pinfunction "1_1") (pintype "passive"))
      (node (ref "R28") (pin "2") (pinfunction "2_2") (pintype "passive"))
    )
    (net (code "52") (name "Net-(IC7B-OUT)") (class "Default")
      (node (ref "IC7") (pin "7") (pinfunction "OUT_7") (pintype "output"))
      (node (ref "R28") (pin "1") (pinfunction "1_1") (pintype "passive"))
      (node (ref "R29") (pin "2") (pinfunction "2_2") (pintype "passive"))
    )
    (net (code "53") (name "Net-(IC9A-+IN)") (class "Default")
      (node (ref "IC9") (pin "3") (pinfunction "+IN_3") (pintype "input"))
      (node (ref "R29") (pin "1") (pinfunction "1_1") (pintype "passive"))
    )
    (net (code "54") (name "Net-(IC9A-OUT)") (class "Default")
      (node (ref "IC9") (pin "1") (pinfunction "OUT_1") (pintype "output"))
      (node (ref "U$7") (pin "1") (pinfunction "B_1") (pintype "passive"))
    )
    (net (code "55") (name "Net-(Q2-G)") (class "Default")
      (node (ref "Q2") (pin "1") (pinfunction "G_1") (pintype "passive"))
      (node (ref "R1") (pin "1") (pinfunction "1_1") (pintype "passive"))
    )
    (net (code "56") (name "Net-(Q3-G)") (class "Default")
      (node (ref "Q3") (pin "1") (pinfunction "G_1") (pintype "passive"))
      (node (ref "R2") (pin "1") (pinfunction "1_1") (pintype "passive"))
    )
    (net (code "57") (name "Net-(Q4-G)") (class "Default")
      (node (ref "Q4") (pin "1") (pinfunction "G_1") (pintype "passive"))
      (node (ref "R3") (pin "1") (pinfunction "1_1") (pintype "passive"))
    )
    (net (code "58") (name "Net-(R24-Pad2)") (class "Default")
      (node (ref "R24") (pin "2") (pinfunction "2_2") (pintype "passive"))
      (node (ref "R25") (pin "1") (pinfunction "1_1") (pintype "passive"))
    )
    (net (code "59") (name "Net-(U$2-OUT)") (class "Default")
      (node (ref "R7") (pin "2") (pinfunction "2_2") (pintype "passive"))
      (node (ref "U$2") (pin "6") (pinfunction "OUT_6") (pintype "bidirectional"))
    )
    (net (code "60") (name "Net-(U$3-OUT)") (class "Default")
      (node (ref "R9") (pin "2") (pinfunction "2_2") (pintype "passive"))
      (node (ref "U$3") (pin "6") (pinfunction "OUT_6") (pintype "bidirectional"))
    )
    (net (code "61") (name "Net-(U$4-FB)") (class "Default")
      (node (ref "R11") (pin "2") (pinfunction "2_2") (pintype "passive"))
      (node (ref "R12") (pin "2") (pinfunction "2_2") (pintype "passive"))
      (node (ref "R4") (pin "1") (pinfunction "1_1") (pintype "passive"))
      (node (ref "U$4") (pin "8") (pinfunction "FB_8") (pintype "bidirectional"))
    )
    (net (code "62") (name "Net-(U$4-RT)") (class "Default")
      (node (ref "R10") (pin "1") (pinfunction "1_1") (pintype "passive"))
      (node (ref "U$4") (pin "1") (pinfunction "RT_1") (pintype "bidirectional"))
    )
    (net (code "63") (name "Net-(U$4-SW)") (class "Default")
      (node (ref "10UH") (pin "2") (pinfunction "2_2") (pintype "passive"))
      (node (ref "U$10") (pin "A") (pinfunction "A_A") (pintype "passive"))
      (node (ref "U$4") (pin "4") (pinfunction "SW_4") (pintype "bidirectional"))
    )
    (net (code "64") (name "Net-(U$4-VC)") (class "Default")
      (node (ref "C11") (pin "2") (pinfunction "2_2") (pintype "passive"))
      (node (ref "C5") (pin "2") (pinfunction "2_2") (pintype "passive"))
      (node (ref "U$4") (pin "9") (pinfunction "VC_9") (pintype "bidirectional"))
    )
    (net (code "65") (name "Net-(U$5-EN)") (class "Default")
      (node (ref "R45") (pin "2") (pinfunction "2_2") (pintype "passive"))
      (node (ref "U$5") (pin "1") (pinfunction "EN_1") (pintype "bidirectional"))
    )
    (net (code "66") (name "Net-(U$5-PG)") (class "Default")
      (node (ref "R13") (pin "2") (pinfunction "2_2") (pintype "passive"))
      (node (ref "U$5") (pin "2") (pinfunction "PG_2") (pintype "bidirectional"))
    )
    (net (code "67") (name "Net-(U$5-SW)") (class "Default")
      (node (ref "0.47UH") (pin "1") (pinfunction "1_1") (pintype "passive"))
      (node (ref "U$5") (pin "6") (pinfunction "SW_6") (pintype "bidirectional"))
    )
    (net (code "68") (name "Net-(U$6-XIN{slash}P2.6)") (class "Default")
      (node (ref "C15") (pin "1") (pinfunction "1_1") (pintype "passive"))
      (node (ref "Q1") (pin "1") (pinfunction "1_1") (pintype "passive"))
      (node (ref "U$6") (pin "6") (pinfunction "XIN/P2.6_6") (pintype "bidirectional"))
    )
    (net (code "69") (name "Net-(U$6-XOUT{slash}P2.7)") (class "Default")
      (node (ref "C14") (pin "1") (pinfunction "1_1") (pintype "passive"))
      (node (ref "Q1") (pin "2") (pinfunction "2_2") (pintype "passive"))
      (node (ref "U$6") (pin "5") (pinfunction "XOUT/P2.7_5") (pintype "bidirectional"))
    )
    (net (code "70") (name "VCC") (class "Default")
      (node (ref "0.47UH") (pin "2") (pinfunction "2_2") (pintype "passive"))
      (node (ref "10UH") (pin "1") (pinfunction "1_1") (pintype "passive"))
      (node (ref "C10") (pin "2") (pinfunction "2_2") (pintype "passive"))
      (node (ref "C21") (pin "2") (pinfunction "2_2") (pintype "passive"))
      (node (ref "C27") (pin "2") (pinfunction "2_2") (pintype "passive"))
      (node (ref "C4") (pin "2") (pinfunction "2_2") (pintype "passive"))
      (node (ref "C_IC1") (pin "2") (pinfunction "2_2") (pintype "passive"))
      (node (ref "C_IC5") (pin "2") (pinfunction "2_2") (pintype "passive"))
      (node (ref "C_IC7") (pin "2") (pinfunction "2_2") (pintype "passive"))
      (node (ref "C_IC9") (pin "2") (pinfunction "2_2") (pintype "passive"))
      (node (ref "FERRITE_BEAD") (pin "2") (pinfunction "2_2") (pintype "passive"))
      (node (ref "IC1") (pin "8") (pinfunction "V+_8") (pintype "power_in"))
      (node (ref "IC5") (pin "8") (pinfunction "V+_8") (pintype "power_in"))
      (node (ref "IC7") (pin "8") (pinfunction "V+_8") (pintype "power_in"))
      (node (ref "IC9") (pin "8") (pinfunction "V+_8") (pintype "power_in"))
      (node (ref "R13") (pin "1") (pinfunction "1_1") (pintype "passive"))
      (node (ref "R14") (pin "2") (pinfunction "2_2") (pintype "passive"))
      (node (ref "R24") (pin "1") (pinfunction "1_1") (pintype "passive"))
      (node (ref "R5") (pin "1") (pinfunction "1_1") (pintype "passive"))
      (node (ref "R6") (pin "1") (pinfunction "1_1") (pintype "passive"))
      (node (ref "R79") (pin "1") (pinfunction "1_1") (pintype "passive"))
      (node (ref "R8") (pin "2") (pinfunction "2_2") (pintype "passive"))
      (node (ref "R80") (pin "1") (pinfunction "1_1") (pintype "passive"))
      (node (ref "R81") (pin "1") (pinfunction "1_1") (pintype "passive"))
      (node (ref "U$19") (pin "3") (pinfunction "VIN_3") (pintype "bidirectional"))
      (node (ref "U$2") (pin "3") (pinfunction "VCC_3") (pintype "bidirectional"))
      (node (ref "U$2") (pin "4") (pinfunction "IN+_4") (pintype "bidirectional"))
      (node (ref "U$3") (pin "3") (pinfunction "VCC_3") (pintype "bidirectional"))
      (node (ref "U$3") (pin "5") (pinfunction "IN-_5") (pintype "bidirectional"))
      (node (ref "U$4") (pin "3") (pinfunction "VIN_3") (pintype "bidirectional"))
      (node (ref "U$5") (pin "3") (pinfunction "FB_3") (pintype "bidirectional"))
      (node (ref "U$5") (pin "4") (pinfunction "VOS_4") (pintype "bidirectional"))
      (node (ref "U$6") (pin "16") (pinfunction "AVCC_16") (pintype "bidirectional"))
      (node (ref "U$7") (pin "2") (pinfunction "C_2") (pintype "passive"))
      (node (ref "VCC") (pin "1") (pinfunction "1_1") (pintype "passive"))
    )
    (net (code "71") (name "unconnected-(U$4-PG-Pad6)") (class "Default")
      (node (ref "U$4") (pin "6") (pinfunction "PG_6") (pintype "bidirectional"))
    )
    (net (code "72") (name "unconnected-(U$6-P1.0{slash}TACLK{slash}ADC10CLK-Pad31)") (class "Default")
      (node (ref "U$6") (pin "31") (pinfunction "P1.0/TACLK/ADC10CLK_31") (pintype "bidirectional"))
    )
    (net (code "73") (name "unconnected-(U$6-P2.0{slash}ACLK{slash}A0-Pad8)") (class "Default")
      (node (ref "U$6") (pin "8") (pinfunction "P2.0/ACLK/A0_8") (pintype "bidirectional"))
    )
    (net (code "74") (name "unconnected-(U$6-P2.3{slash}TA1{slash}A3{slash}VREF−{slash}VEREF--Pad29)") (class "Default")
      (node (ref "U$6") (pin "29") (pinfunction "P2.3/TA1/A3/VREF−/VEREF-_29") (pintype "bidirectional"))
    )
    (net (code "75") (name "unconnected-(U$6-P2.4{slash}TA2{slash}A4{slash}VREF+{slash}VEREF+-Pad30)") (class "Default")
      (node (ref "U$6") (pin "30") (pinfunction "P2.4/TA2/A4/VREF+/VEREF+_30") (pintype "bidirectional"))
    )
    (net (code "76") (name "unconnected-(U$6-P2.5{slash}ROSC-Pad3)") (class "Default")
      (node (ref "U$6") (pin "3") (pinfunction "P2.5/ROSC_3") (pintype "bidirectional"))
    )
    (net (code "77") (name "unconnected-(U$6-P3.0{slash}UCB0STE{slash}UCA0CLK{slash}A5-Pad11)") (class "Default")
      (node (ref "U$6") (pin "11") (pinfunction "P3.0/UCB0STE/UCA0CLK/A5_11") (pintype "bidirectional"))
    )
    (net (code "78") (name "unconnected-(U$6-P3.3{slash}UCB0CLK{slash}UCA0STE-Pad14)") (class "Default")
      (node (ref "U$6") (pin "14") (pinfunction "P3.3/UCB0CLK/UCA0STE_14") (pintype "bidirectional"))
    )
    (net (code "79") (name "unconnected-(U$6-P3.4{slash}UCA0TXD{slash}UCA0SIMO-Pad25)") (class "Default")
      (node (ref "U$6") (pin "25") (pinfunction "P3.4/UCA0TXD/UCA0SIMO_25") (pintype "bidirectional"))
    )
    (net (code "80") (name "unconnected-(U$6-P3.5{slash}UCA0RXD{slash}UCA0SOMI-Pad26)") (class "Default")
      (node (ref "U$6") (pin "26") (pinfunction "P3.5/UCA0RXD/UCA0SOMI_26") (pintype "bidirectional"))
    )
    (net (code "81") (name "unconnected-(U$6-P4.0{slash}TB0-Pad17)") (class "Default")
      (node (ref "U$6") (pin "17") (pinfunction "P4.0/TB0_17") (pintype "bidirectional"))
    )
    (net (code "82") (name "unconnected-(U$6-P4.1{slash}TB1-Pad18)") (class "Default")
      (node (ref "U$6") (pin "18") (pinfunction "P4.1/TB1_18") (pintype "bidirectional"))
    )
    (net (code "83") (name "unconnected-(U$6-P4.2{slash}TB2-Pad19)") (class "Default")
      (node (ref "U$6") (pin "19") (pinfunction "P4.2/TB2_19") (pintype "bidirectional"))
    )
    (net (code "84") (name "unconnected-(U$6-P4.7{slash}TBCLK-Pad24)") (class "Default")
      (node (ref "U$6") (pin "24") (pinfunction "P4.7/TBCLK_24") (pintype "bidirectional"))
    )
    (net (code "85") (name "unconnected-(U$16-OC-Pad5)") (class "Default")
      (node (ref "U$16") (pin "5") (pinfunction "OC_5") (pintype "bidirectional"))
    )
    (net (code "86") (name "unconnected-(U$17-OC-Pad5)") (class "Default")
      (node (ref "U$17") (pin "5") (pinfunction "OC_5") (pintype "bidirectional"))
    )
    (net (code "87") (name "unconnected-(U$18-OC-Pad5)") (class "Default")
      (node (ref "U$18") (pin "5") (pinfunction "OC_5") (pintype "bidirectional"))
    )
    (net (code "88") (name "unconnected-(U$19-NC1-Pad1)") (class "Default")
      (node (ref "U$19") (pin "1") (pinfunction "NC1_1") (pintype "bidirectional"))
    )
    (net (code "89") (name "unconnected-(U$19-NC2-Pad5)") (class "Default")
      (node (ref "U$19") (pin "5") (pinfunction "NC2_5") (pintype "bidirectional"))
    )
    (net (code "90") (name "unconnected-(U$19-NC3-Pad6)") (class "Default")
      (node (ref "U$19") (pin "6") (pinfunction "NC3_6") (pintype "bidirectional"))
    )
  )
)
